# Fount.net
KiCad netlist of a schematic drawn in Altium Designer
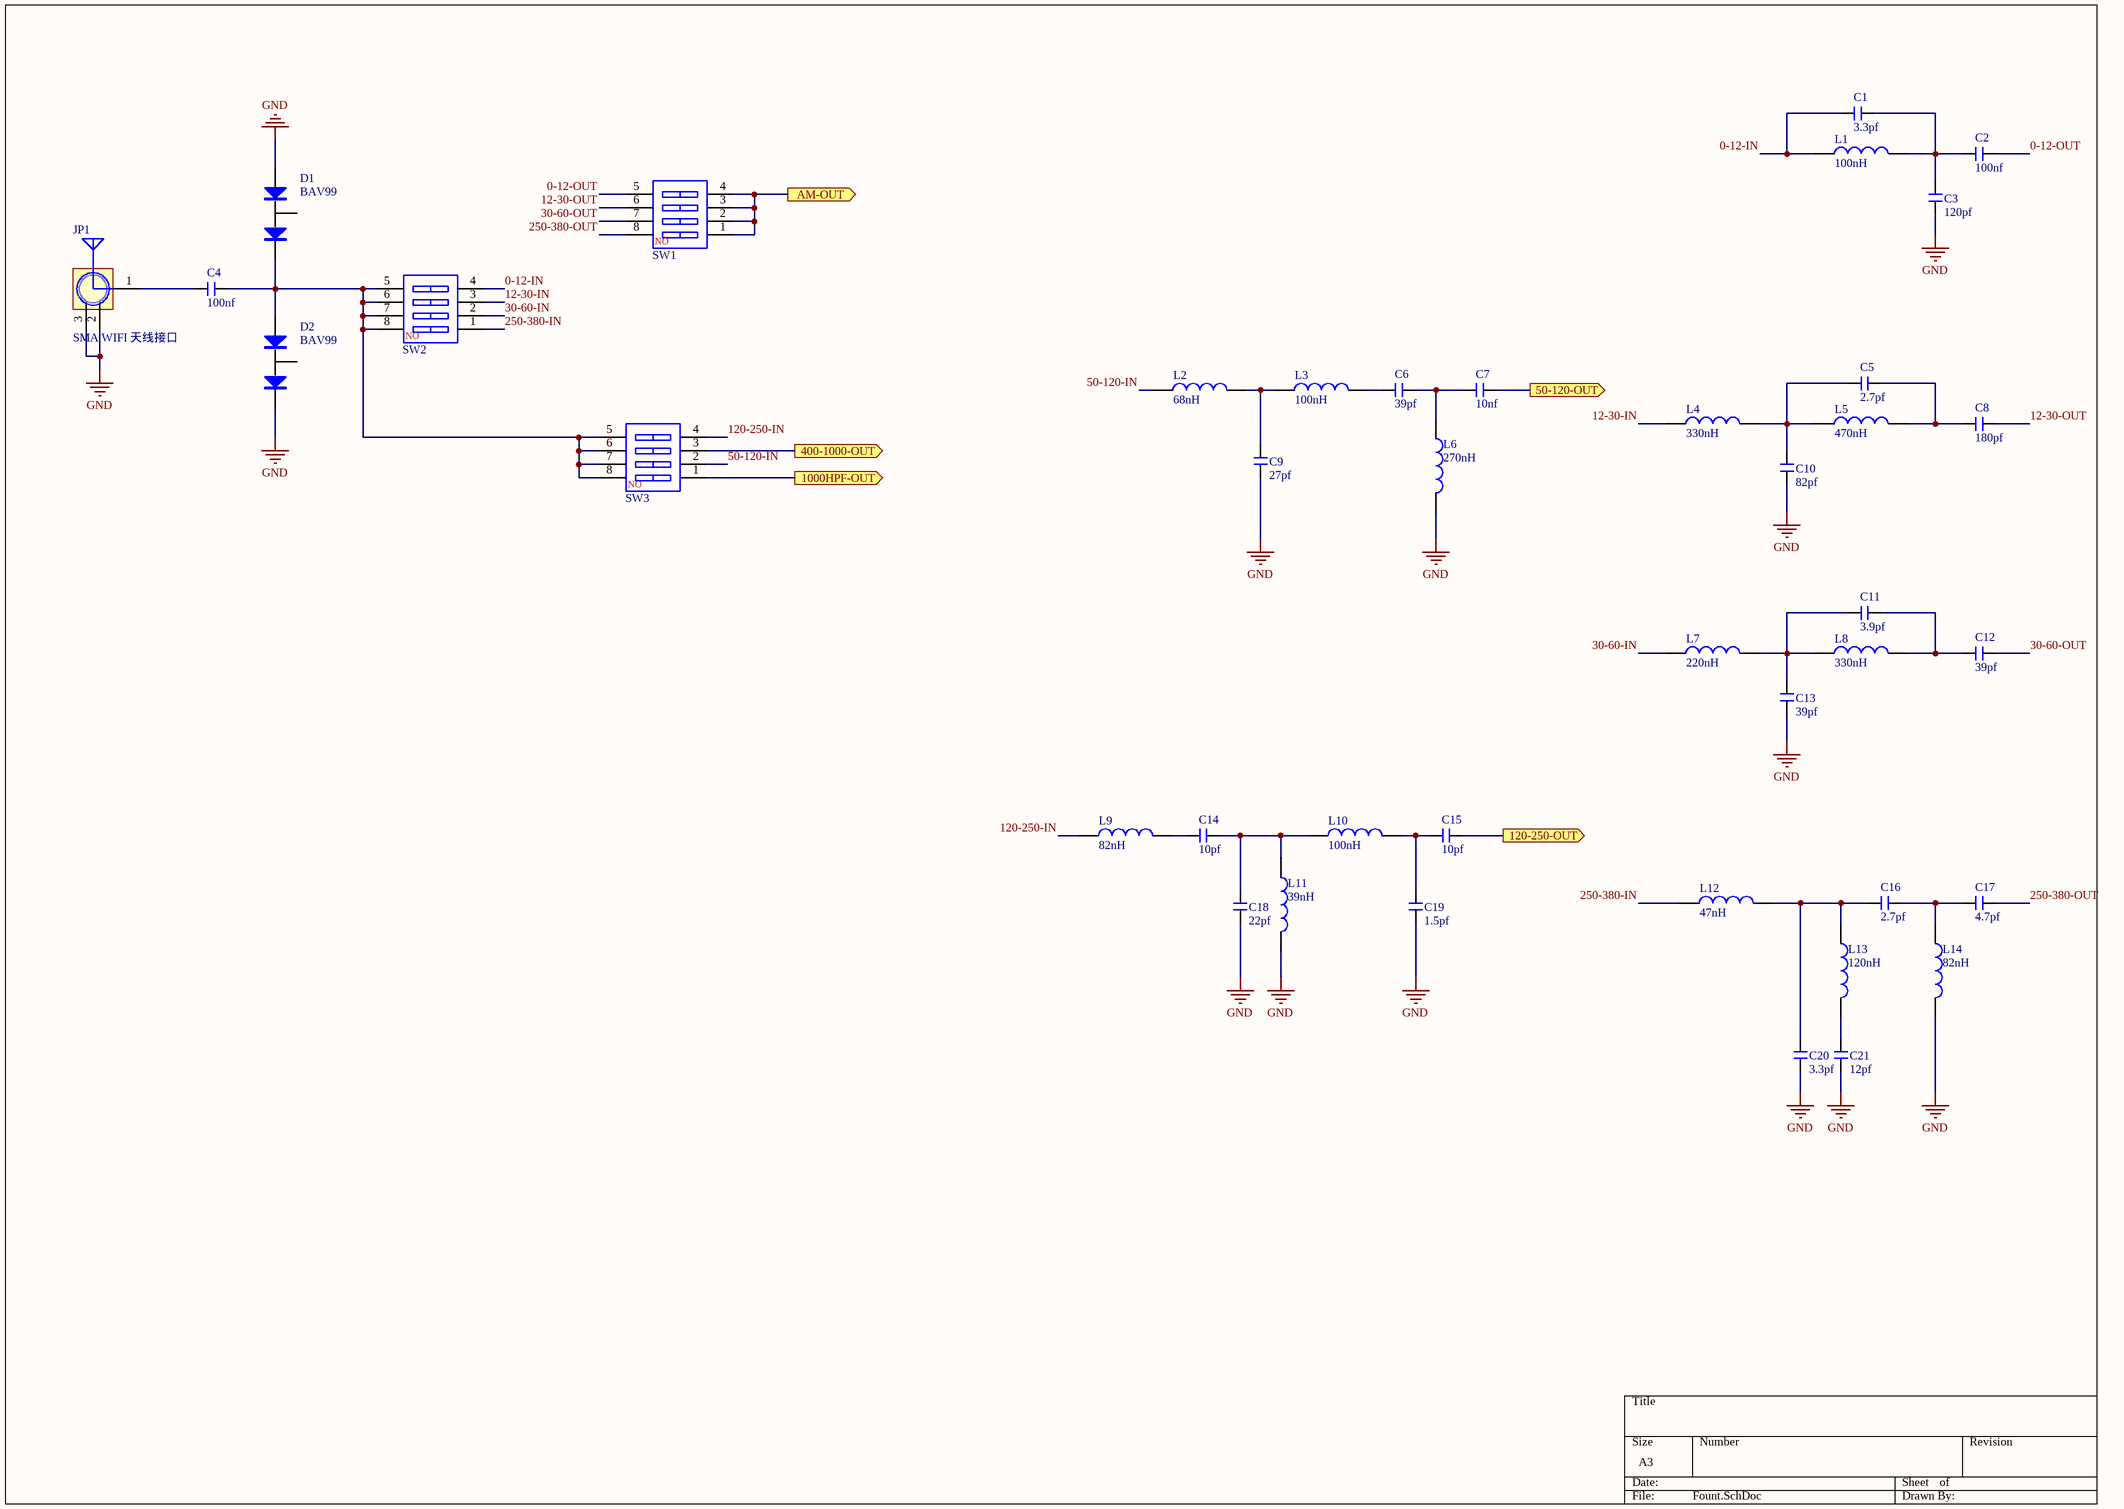
[diagram p0: Fount.SchDoc]

(export (version "E")
  (design (tool "Eeschema 10.0.6"))
  (components
    (comp (ref "C1")
      (value "3.3pf")
      (footprint "C 0603_M")
      (description "无极性贴片电容")
      (fields (field (name "版权归属") "源创客"))
      (libsource (lib "电阻-电容-电感") (part "C"))
    )
    (comp (ref "C2")
      (value "100nf")
      (footprint "C 0603_M")
      (description "无极性贴片电容")
      (fields (field (name "版权归属") "源创客"))
      (libsource (lib "电阻-电容-电感") (part "C"))
    )
    (comp (ref "C3")
      (value "120pf")
      (footprint "C 0603_M")
      (description "无极性贴片电容")
      (fields (field (name "版权归属") "源创客"))
      (libsource (lib "电阻-电容-电感") (part "C"))
    )
    (comp (ref "C4")
      (value "100nf")
      (footprint "C 0603_M")
      (description "无极性贴片电容")
      (fields (field (name "版权归属") "源创客"))
      (libsource (lib "电阻-电容-电感") (part "C"))
    )
    (comp (ref "C5")
      (value "2.7pf")
      (footprint "C 0603_M")
      (description "无极性贴片电容")
      (fields (field (name "版权归属") "源创客"))
      (libsource (lib "电阻-电容-电感") (part "C"))
    )
    (comp (ref "C6")
      (value "39pf")
      (footprint "C 0603_M")
      (description "无极性贴片电容")
      (fields (field (name "版权归属") "源创客"))
      (libsource (lib "电阻-电容-电感") (part "C"))
    )
    (comp (ref "C7")
      (value "10nf")
      (footprint "C 0603_M")
      (description "无极性贴片电容")
      (fields (field (name "版权归属") "源创客"))
      (libsource (lib "电阻-电容-电感") (part "C"))
    )
    (comp (ref "C8")
      (value "180pf")
      (footprint "C 0603_M")
      (description "无极性贴片电容")
      (fields (field (name "版权归属") "源创客"))
      (libsource (lib "电阻-电容-电感") (part "C"))
    )
    (comp (ref "C9")
      (value "27pf")
      (footprint "C 0603_M")
      (description "无极性贴片电容")
      (fields (field (name "版权归属") "源创客"))
      (libsource (lib "电阻-电容-电感") (part "C"))
    )
    (comp (ref "C10")
      (value "82pf")
      (footprint "C 0603_M")
      (description "无极性贴片电容")
      (fields (field (name "版权归属") "源创客"))
      (libsource (lib "电阻-电容-电感") (part "C"))
    )
    (comp (ref "C11")
      (value "3.9pf")
      (footprint "C 0603_M")
      (description "无极性贴片电容")
      (fields (field (name "版权归属") "源创客"))
      (libsource (lib "电阻-电容-电感") (part "C"))
    )
    (comp (ref "C12")
      (value "39pf")
      (footprint "C 0603_M")
      (description "无极性贴片电容")
      (fields (field (name "版权归属") "源创客"))
      (libsource (lib "电阻-电容-电感") (part "C"))
    )
    (comp (ref "C13")
      (value "39pf")
      (footprint "C 0603_M")
      (description "无极性贴片电容")
      (fields (field (name "版权归属") "源创客"))
      (libsource (lib "电阻-电容-电感") (part "C"))
    )
    (comp (ref "C14")
      (value "10pf")
      (footprint "C 0603_M")
      (description "无极性贴片电容")
      (fields (field (name "版权归属") "源创客"))
      (libsource (lib "电阻-电容-电感") (part "C"))
    )
    (comp (ref "C15")
      (value "10pf")
      (footprint "C 0603_M")
      (description "无极性贴片电容")
      (fields (field (name "版权归属") "源创客"))
      (libsource (lib "电阻-电容-电感") (part "C"))
    )
    (comp (ref "C16")
      (value "2.7pf")
      (footprint "C 0603_M")
      (description "无极性贴片电容")
      (fields (field (name "版权归属") "源创客"))
      (libsource (lib "电阻-电容-电感") (part "C"))
    )
    (comp (ref "C17")
      (value "4.7pf")
      (footprint "C 0603_M")
      (description "无极性贴片电容")
      (fields (field (name "版权归属") "源创客"))
      (libsource (lib "电阻-电容-电感") (part "C"))
    )
    (comp (ref "C18")
      (value "22pf")
      (footprint "C 0603_M")
      (description "无极性贴片电容")
      (fields (field (name "版权归属") "源创客"))
      (libsource (lib "电阻-电容-电感") (part "C"))
    )
    (comp (ref "C19")
      (value "1.5pf")
      (footprint "C 0603_M")
      (description "无极性贴片电容")
      (fields (field (name "版权归属") "源创客"))
      (libsource (lib "电阻-电容-电感") (part "C"))
    )
    (comp (ref "C20")
      (value "3.3pf")
      (footprint "C 0603_M")
      (description "无极性贴片电容")
      (fields (field (name "版权归属") "源创客"))
      (libsource (lib "电阻-电容-电感") (part "C"))
    )
    (comp (ref "C21")
      (value "12pf")
      (footprint "C 0603_M")
      (description "无极性贴片电容")
      (fields (field (name "版权归属") "源创客"))
      (libsource (lib "电阻-电容-电感") (part "C"))
    )
    (comp (ref "D1")
      (value "BAV99")
      (footprint "SOT23-3M")
      (description "天线保护二极管")
      (libsource (lib "二极管-整流桥") (part "BAV99"))
    )
    (comp (ref "D2")
      (value "BAV99")
      (footprint "SOT23-3M")
      (description "天线保护二极管")
      (libsource (lib "二极管-整流桥") (part "BAV99"))
    )
    (comp (ref "JP1")
      (value "SMA WIFI 天线接口")
      (footprint "SMA-KE")
      (description "SMA-2.4G射频天线接口")
      (fields (field (name "版权归属") "源创客"))
      (libsource (lib "天线") (part "SMA"))
    )
    (comp (ref "L1")
      (value "100nH")
      (footprint "L 0603")
      (description "小功率贴片电感")
      (fields (field (name "版权归属") "源创客"))
      (libsource (lib "电阻-电容-电感") (part "L"))
    )
    (comp (ref "L2")
      (value "68nH")
      (footprint "L 0603")
      (description "小功率贴片电感")
      (fields (field (name "版权归属") "源创客"))
      (libsource (lib "电阻-电容-电感") (part "L"))
    )
    (comp (ref "L3")
      (value "100nH")
      (footprint "L 0603")
      (description "小功率贴片电感")
      (fields (field (name "版权归属") "源创客"))
      (libsource (lib "电阻-电容-电感") (part "L"))
    )
    (comp (ref "L4")
      (value "330nH")
      (footprint "L 0603")
      (description "小功率贴片电感")
      (fields (field (name "版权归属") "源创客"))
      (libsource (lib "电阻-电容-电感") (part "L"))
    )
    (comp (ref "L5")
      (value "470nH")
      (footprint "L 0603")
      (description "小功率贴片电感")
      (fields (field (name "版权归属") "源创客"))
      (libsource (lib "电阻-电容-电感") (part "L"))
    )
    (comp (ref "L6")
      (value "270nH")
      (footprint "L 0603")
      (description "小功率贴片电感")
      (fields (field (name "版权归属") "源创客"))
      (libsource (lib "电阻-电容-电感") (part "L"))
    )
    (comp (ref "L7")
      (value "220nH")
      (footprint "L 0603")
      (description "小功率贴片电感")
      (fields (field (name "版权归属") "源创客"))
      (libsource (lib "电阻-电容-电感") (part "L"))
    )
    (comp (ref "L8")
      (value "330nH")
      (footprint "L 0603")
      (description "小功率贴片电感")
      (fields (field (name "版权归属") "源创客"))
      (libsource (lib "电阻-电容-电感") (part "L"))
    )
    (comp (ref "L9")
      (value "82nH")
      (footprint "L 0603")
      (description "小功率贴片电感")
      (fields (field (name "版权归属") "源创客"))
      (libsource (lib "电阻-电容-电感") (part "L"))
    )
    (comp (ref "L10")
      (value "100nH")
      (footprint "L 0603")
      (description "小功率贴片电感")
      (fields (field (name "版权归属") "源创客"))
      (libsource (lib "电阻-电容-电感") (part "L"))
    )
    (comp (ref "L11")
      (value "39nH")
      (footprint "L 0603")
      (description "小功率贴片电感")
      (fields (field (name "版权归属") "源创客"))
      (libsource (lib "电阻-电容-电感") (part "L"))
    )
    (comp (ref "L12")
      (value "47nH")
      (footprint "L 0603")
      (description "小功率贴片电感")
      (fields (field (name "版权归属") "源创客"))
      (libsource (lib "电阻-电容-电感") (part "L"))
    )
    (comp (ref "L13")
      (value "120nH")
      (footprint "L 0603")
      (description "小功率贴片电感")
      (fields (field (name "版权归属") "源创客"))
      (libsource (lib "电阻-电容-电感") (part "L"))
    )
    (comp (ref "L14")
      (value "82nH")
      (footprint "L 0603")
      (description "小功率贴片电感")
      (fields (field (name "版权归属") "源创客"))
      (libsource (lib "电阻-电容-电感") (part "L"))
    )
    (comp (ref "SW1")
      (value "CSW-4P")
      (footprint "CSW1.27 SMD-4P")
      (description "4路编码开关")
      (fields (field (name "版权归属") "源创客"))
      (libsource (lib "按键-开关") (part "CSW-4P"))
    )
    (comp (ref "SW2")
      (value "CSW-4P")
      (footprint "CSW1.27 SMD-4P")
      (description "4路编码开关")
      (fields (field (name "版权归属") "源创客"))
      (libsource (lib "按键-开关") (part "CSW-4P"))
    )
    (comp (ref "SW3")
      (value "CSW-4P")
      (footprint "CSW1.27 SMD-4P")
      (description "4路编码开关")
      (fields (field (name "版权归属") "源创客"))
      (libsource (lib "按键-开关") (part "CSW-4P"))
    )
  )
  (nets
    (net (code "1") (name "/0-12-IN") (class "Default")
      (node (ref "C1") (pin "1") (pinfunction "1_1") (pintype "passive"))
      (node (ref "L1") (pin "1") (pinfunction "1_1") (pintype "passive"))
      (node (ref "SW2") (pin "4") (pinfunction "4_4") (pintype "passive"))
    )
    (net (code "2") (name "/0-12-OUT") (class "Default")
      (node (ref "C2") (pin "2") (pinfunction "2_2") (pintype "passive"))
      (node (ref "SW1") (pin "5") (pinfunction "5_5") (pintype "passive"))
    )
    (net (code "3") (name "/12-30-IN") (class "Default")
      (node (ref "L4") (pin "1") (pinfunction "1_1") (pintype "passive"))
      (node (ref "SW2") (pin "3") (pinfunction "3_3") (pintype "passive"))
    )
    (net (code "4") (name "/12-30-OUT") (class "Default")
      (node (ref "C8") (pin "2") (pinfunction "2_2") (pintype "passive"))
      (node (ref "SW1") (pin "6") (pinfunction "6_6") (pintype "passive"))
    )
    (net (code "5") (name "/30-60-IN") (class "Default")
      (node (ref "L7") (pin "1") (pinfunction "1_1") (pintype "passive"))
      (node (ref "SW2") (pin "2") (pinfunction "2_2") (pintype "passive"))
    )
    (net (code "6") (name "/30-60-OUT") (class "Default")
      (node (ref "C12") (pin "2") (pinfunction "2_2") (pintype "passive"))
      (node (ref "SW1") (pin "7") (pinfunction "7_7") (pintype "passive"))
    )
    (net (code "7") (name "/50-120-IN") (class "Default")
      (node (ref "L2") (pin "1") (pinfunction "1_1") (pintype "passive"))
      (node (ref "SW3") (pin "2") (pinfunction "2_2") (pintype "passive"))
    )
    (net (code "8") (name "/50-120-OUT") (class "Default")
      (node (ref "C7") (pin "2") (pinfunction "2_2") (pintype "passive"))
    )
    (net (code "9") (name "/120-250-IN") (class "Default")
      (node (ref "L9") (pin "1") (pinfunction "1_1") (pintype "passive"))
      (node (ref "SW3") (pin "4") (pinfunction "4_4") (pintype "passive"))
    )
    (net (code "10") (name "/120-250-OUT") (class "Default")
      (node (ref "C15") (pin "2") (pinfunction "2_2") (pintype "passive"))
    )
    (net (code "11") (name "/250-380-IN") (class "Default")
      (node (ref "L12") (pin "1") (pinfunction "1_1") (pintype "passive"))
      (node (ref "SW2") (pin "1") (pinfunction "1_1") (pintype "passive"))
    )
    (net (code "12") (name "/250-380-OUT") (class "Default")
      (node (ref "C17") (pin "2") (pinfunction "2_2") (pintype "passive"))
      (node (ref "SW1") (pin "8") (pinfunction "8_8") (pintype "passive"))
    )
    (net (code "13") (name "/400-1000-OUT") (class "Default")
      (node (ref "SW3") (pin "3") (pinfunction "3_3") (pintype "passive"))
    )
    (net (code "14") (name "/1000HPF-OUT") (class "Default")
      (node (ref "SW3") (pin "1") (pinfunction "1_1") (pintype "passive"))
    )
    (net (code "15") (name "/AM-OUT") (class "Default")
      (node (ref "SW1") (pin "1") (pinfunction "1_1") (pintype "passive"))
      (node (ref "SW1") (pin "2") (pinfunction "2_2") (pintype "passive"))
      (node (ref "SW1") (pin "3") (pinfunction "3_3") (pintype "passive"))
      (node (ref "SW1") (pin "4") (pinfunction "4_4") (pintype "passive"))
    )
    (net (code "16") (name "GND") (class "Default")
      (node (ref "C10") (pin "2") (pinfunction "2_2") (pintype "passive"))
      (node (ref "C13") (pin "2") (pinfunction "2_2") (pintype "passive"))
      (node (ref "C18") (pin "1") (pinfunction "1_1") (pintype "passive"))
      (node (ref "C19") (pin "1") (pinfunction "1_1") (pintype "passive"))
      (node (ref "C20") (pin "1") (pinfunction "1_1") (pintype "passive"))
      (node (ref "C21") (pin "1") (pinfunction "1_1") (pintype "passive"))
      (node (ref "C3") (pin "1") (pinfunction "1_1") (pintype "passive"))
      (node (ref "C9") (pin "1") (pinfunction "1_1") (pintype "passive"))
      (node (ref "D1") (pin "1") (pinfunction "1_1") (pintype "passive"))
      (node (ref "D2") (pin "2") (pinfunction "2_2") (pintype "passive"))
      (node (ref "JP1") (pin "2") (pinfunction "GND_2") (pintype "passive"))
      (node (ref "JP1") (pin "3") (pinfunction "GND_3") (pintype "passive"))
      (node (ref "L11") (pin "2") (pinfunction "2_2") (pintype "passive"))
      (node (ref "L14") (pin "2") (pinfunction "2_2") (pintype "passive"))
      (node (ref "L6") (pin "2") (pinfunction "2_2") (pintype "passive"))
    )
    (net (code "17") (name "Net-(C1-Pad2)") (class "Default")
      (node (ref "C1") (pin "2") (pinfunction "2_2") (pintype "passive"))
      (node (ref "C2") (pin "1") (pinfunction "1_1") (pintype "passive"))
      (node (ref "C3") (pin "2") (pinfunction "2_2") (pintype "passive"))
      (node (ref "L1") (pin "2") (pinfunction "2_2") (pintype "passive"))
    )
    (net (code "18") (name "Net-(C4-Pad2)") (class "Default")
      (node (ref "C4") (pin "2") (pinfunction "2_2") (pintype "passive"))
      (node (ref "D1") (pin "2") (pinfunction "2_2") (pintype "passive"))
      (node (ref "D2") (pin "1") (pinfunction "1_1") (pintype "passive"))
      (node (ref "SW2") (pin "5") (pinfunction "5_5") (pintype "passive"))
      (node (ref "SW2") (pin "6") (pinfunction "6_6") (pintype "passive"))
      (node (ref "SW2") (pin "7") (pinfunction "7_7") (pintype "passive"))
      (node (ref "SW2") (pin "8") (pinfunction "8_8") (pintype "passive"))
      (node (ref "SW3") (pin "5") (pinfunction "5_5") (pintype "passive"))
      (node (ref "SW3") (pin "6") (pinfunction "6_6") (pintype "passive"))
      (node (ref "SW3") (pin "7") (pinfunction "7_7") (pintype "passive"))
      (node (ref "SW3") (pin "8") (pinfunction "8_8") (pintype "passive"))
    )
    (net (code "19") (name "Net-(C5-Pad2)") (class "Default")
      (node (ref "C5") (pin "2") (pinfunction "2_2") (pintype "passive"))
      (node (ref "C8") (pin "1") (pinfunction "1_1") (pintype "passive"))
      (node (ref "L5") (pin "2") (pinfunction "2_2") (pintype "passive"))
    )
    (net (code "20") (name "Net-(C6-Pad1)") (class "Default")
      (node (ref "C6") (pin "1") (pinfunction "1_1") (pintype "passive"))
      (node (ref "L3") (pin "2") (pinfunction "2_2") (pintype "passive"))
    )
    (net (code "21") (name "Net-(C6-Pad2)") (class "Default")
      (node (ref "C6") (pin "2") (pinfunction "2_2") (pintype "passive"))
      (node (ref "C7") (pin "1") (pinfunction "1_1") (pintype "passive"))
      (node (ref "L6") (pin "1") (pinfunction "1_1") (pintype "passive"))
    )
    (net (code "22") (name "Net-(C9-Pad2)") (class "Default")
      (node (ref "C9") (pin "2") (pinfunction "2_2") (pintype "passive"))
      (node (ref "L2") (pin "2") (pinfunction "2_2") (pintype "passive"))
      (node (ref "L3") (pin "1") (pinfunction "1_1") (pintype "passive"))
    )
    (net (code "23") (name "Net-(C10-Pad1)") (class "Default")
      (node (ref "C10") (pin "1") (pinfunction "1_1") (pintype "passive"))
      (node (ref "C5") (pin "1") (pinfunction "1_1") (pintype "passive"))
      (node (ref "L4") (pin "2") (pinfunction "2_2") (pintype "passive"))
      (node (ref "L5") (pin "1") (pinfunction "1_1") (pintype "passive"))
    )
    (net (code "24") (name "Net-(C11-Pad1)") (class "Default")
      (node (ref "C11") (pin "1") (pinfunction "1_1") (pintype "passive"))
      (node (ref "C13") (pin "1") (pinfunction "1_1") (pintype "passive"))
      (node (ref "L7") (pin "2") (pinfunction "2_2") (pintype "passive"))
      (node (ref "L8") (pin "1") (pinfunction "1_1") (pintype "passive"))
    )
    (net (code "25") (name "Net-(C11-Pad2)") (class "Default")
      (node (ref "C11") (pin "2") (pinfunction "2_2") (pintype "passive"))
      (node (ref "C12") (pin "1") (pinfunction "1_1") (pintype "passive"))
      (node (ref "L8") (pin "2") (pinfunction "2_2") (pintype "passive"))
    )
    (net (code "26") (name "Net-(C14-Pad1)") (class "Default")
      (node (ref "C14") (pin "1") (pinfunction "1_1") (pintype "passive"))
      (node (ref "L9") (pin "2") (pinfunction "2_2") (pintype "passive"))
    )
    (net (code "27") (name "Net-(C14-Pad2)") (class "Default")
      (node (ref "C14") (pin "2") (pinfunction "2_2") (pintype "passive"))
      (node (ref "C18") (pin "2") (pinfunction "2_2") (pintype "passive"))
      (node (ref "L10") (pin "1") (pinfunction "1_1") (pintype "passive"))
      (node (ref "L11") (pin "1") (pinfunction "1_1") (pintype "passive"))
    )
    (net (code "28") (name "Net-(C15-Pad1)") (class "Default")
      (node (ref "C15") (pin "1") (pinfunction "1_1") (pintype "passive"))
      (node (ref "C19") (pin "2") (pinfunction "2_2") (pintype "passive"))
      (node (ref "L10") (pin "2") (pinfunction "2_2") (pintype "passive"))
    )
    (net (code "29") (name "Net-(C16-Pad1)") (class "Default")
      (node (ref "C16") (pin "1") (pinfunction "1_1") (pintype "passive"))
      (node (ref "C20") (pin "2") (pinfunction "2_2") (pintype "passive"))
      (node (ref "L12") (pin "2") (pinfunction "2_2") (pintype "passive"))
      (node (ref "L13") (pin "1") (pinfunction "1_1") (pintype "passive"))
    )
    (net (code "30") (name "Net-(C16-Pad2)") (class "Default")
      (node (ref "C16") (pin "2") (pinfunction "2_2") (pintype "passive"))
      (node (ref "C17") (pin "1") (pinfunction "1_1") (pintype "passive"))
      (node (ref "L14") (pin "1") (pinfunction "1_1") (pintype "passive"))
    )
    (net (code "31") (name "Net-(C21-Pad2)") (class "Default")
      (node (ref "C21") (pin "2") (pinfunction "2_2") (pintype "passive"))
      (node (ref "L13") (pin "2") (pinfunction "2_2") (pintype "passive"))
    )
    (net (code "32") (name "Net-(JP1-ANT)") (class "Default")
      (node (ref "C4") (pin "1") (pinfunction "1_1") (pintype "passive"))
      (node (ref "JP1") (pin "1") (pinfunction "ANT_1") (pintype "passive"))
    )
    (net (code "33") (name "unconnected-(D1-Pad3)") (class "Default")
      (node (ref "D1") (pin "3") (pinfunction "3_3") (pintype "passive"))
    )
    (net (code "34") (name "unconnected-(D2-Pad3)") (class "Default")
      (node (ref "D2") (pin "3") (pinfunction "3_3") (pintype "passive"))
    )
  )
)
